# IMX_Supporting_Circuits.net
KiCad netlist of a schematic drawn in Altium Designer
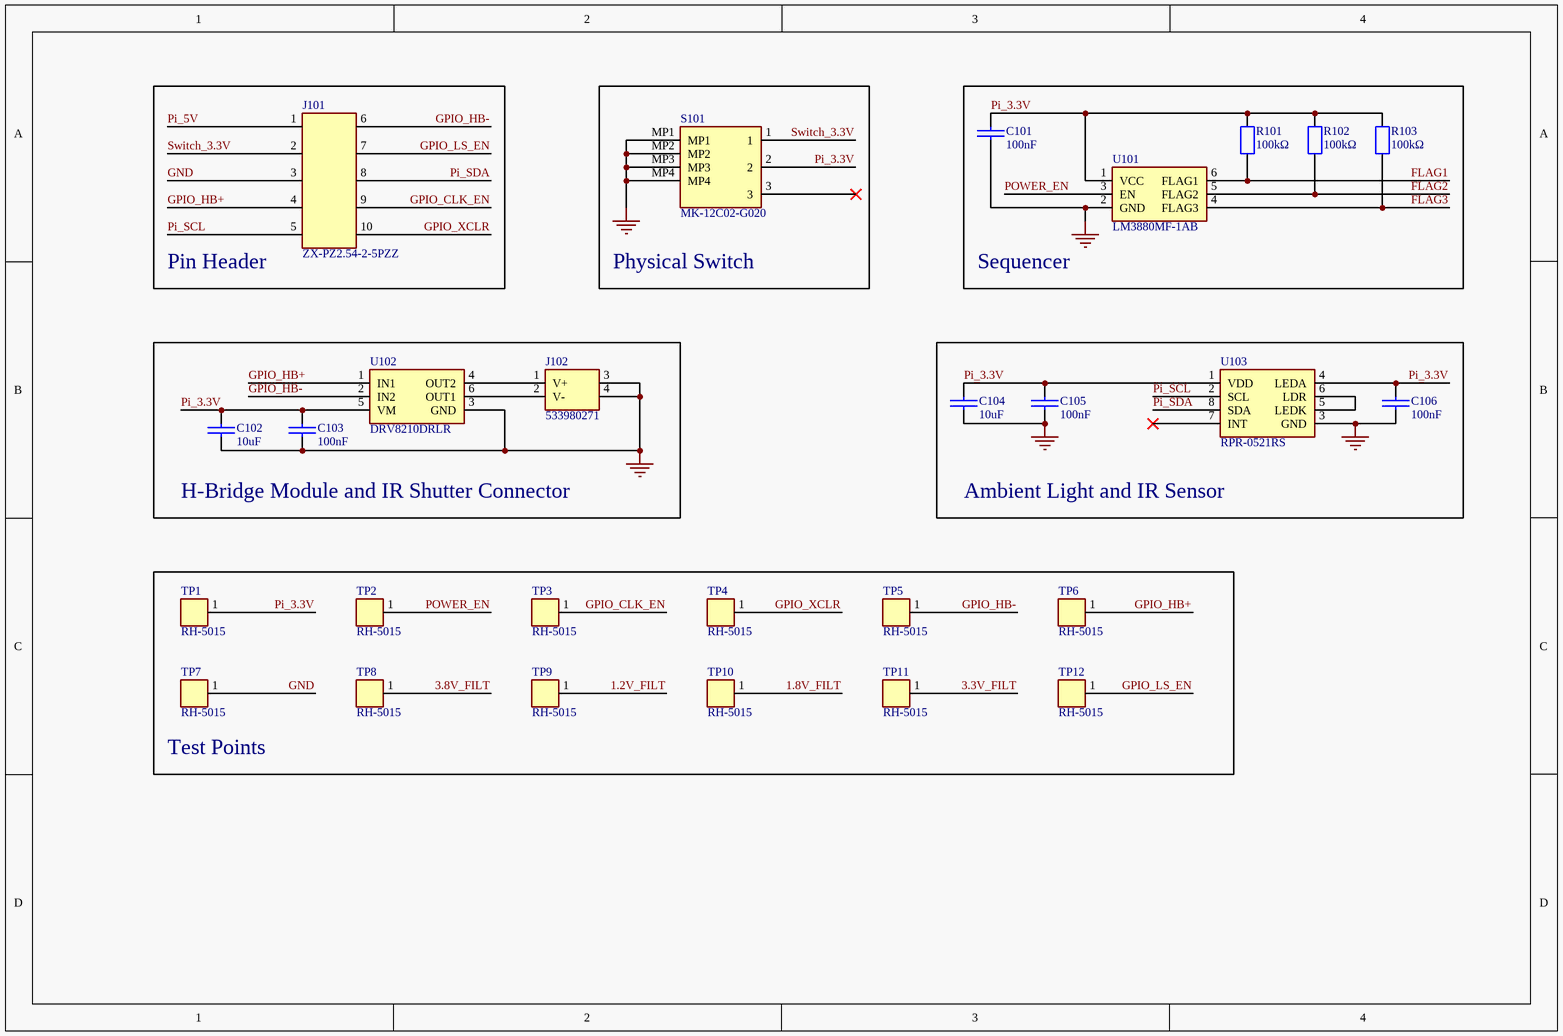
[diagram p0: IMX_Supporting Circuits.SchDoc]

(export (version "E")
  (design (tool "Eeschema 10.0.6"))
  (components
    (comp (ref "C101")
      (value "100nF")
      (footprint "Capacitor, 0402")
      (description "Ceramic Capacitor, 16V, 10% +/- Tol, X7R, 0.1uF, SMD, 0402, #CL05B104KO5NNNC, JLC#C1525")
      (libsource (lib "Component Library") (part "Capacitor, 0402, 100nF"))
    )
    (comp (ref "C102")
      (value "10uF")
      (footprint "Capacitor, 0603")
      (description "Ceramic Capacitor, 10V, 10% +/- Tol, X7R, 10uF, SMD, 0603, #GRM188Z71A106KA73D, JLC#C2959727")
      (libsource (lib "Component Library") (part "Capacitor, 0603, 10uF"))
    )
    (comp (ref "C103")
      (value "100nF")
      (footprint "Capacitor, 0402")
      (description "Ceramic Capacitor, 16V, 10% +/- Tol, X7R, 0.1uF, SMD, 0402, #CL05B104KO5NNNC, JLC#C1525")
      (libsource (lib "Component Library") (part "Capacitor, 0402, 100nF"))
    )
    (comp (ref "C104")
      (value "10uF")
      (footprint "Capacitor, 0603")
      (description "Ceramic Capacitor, 10V, 10% +/- Tol, X7R, 10uF, SMD, 0603, #GRM188Z71A106KA73D, JLC#C2959727")
      (libsource (lib "Component Library") (part "Capacitor, 0603, 10uF"))
    )
    (comp (ref "C105")
      (value "100nF")
      (footprint "Capacitor, 0402")
      (description "Ceramic Capacitor, 16V, 10% +/- Tol, X7R, 0.1uF, SMD, 0402, #CL05B104KO5NNNC, JLC#C1525")
      (libsource (lib "Component Library") (part "Capacitor, 0402, 100nF"))
    )
    (comp (ref "C106")
      (value "100nF")
      (footprint "Capacitor, 0402")
      (description "Ceramic Capacitor, 16V, 10% +/- Tol, X7R, 0.1uF, SMD, 0402, #CL05B104KO5NNNC, JLC#C1525")
      (libsource (lib "Component Library") (part "Capacitor, 0402, 100nF"))
    )
    (comp (ref "J101")
      (value "ZX-PZ2.54-2-5PZZ")
      (footprint "Pin Header, DIP 2x5, 2.54mm")
      (libsource (lib "Component Library") (part "Pin Header, DIP 2x5, 2.54mm"))
    )
    (comp (ref "J102")
      (value "533980271")
      (footprint "Molex PicoBlade, Wire To Board 1x2, 533980271")
      (libsource (lib "Component Library") (part "Molex PicoBlade, Wire To Board 1x2"))
    )
    (comp (ref "R101")
      (value "100kΩ")
      (footprint "Resistor, 0603, Yageo")
      (description "Thick Film Resistor, ±1%, ±100ppm/℃, -55℃~+155℃, 0603, 100kΩ, #RC0603FR-07100KL, JLC#C14675")
      (libsource (lib "Component Library") (part "Resistor, 0603, 100kΩ"))
    )
    (comp (ref "R102")
      (value "100kΩ")
      (footprint "Resistor, 0603, Yageo")
      (description "Thick Film Resistor, ±1%, ±100ppm/℃, -55℃~+155℃, 0603, 100kΩ, #RC0603FR-07100KL, JLC#C14675")
      (libsource (lib "Component Library") (part "Resistor, 0603, 100kΩ"))
    )
    (comp (ref "R103")
      (value "100kΩ")
      (footprint "Resistor, 0603, Yageo")
      (description "Thick Film Resistor, ±1%, ±100ppm/℃, -55℃~+155℃, 0603, 100kΩ, #RC0603FR-07100KL, JLC#C14675")
      (libsource (lib "Component Library") (part "Resistor, 0603, 100kΩ"))
    )
    (comp (ref "S101")
      (value "MK-12C02-G020")
      (footprint "Swich, 1A, Single Pole Double Throw, MK-12C02-G020")
      (libsource (lib "Component Library") (part "Swich, 1A, Single Pole Double Throw"))
    )
    (comp (ref "TP1")
      (value "RH-5015")
      (footprint "Test Point")
      (description "Pogo Pin Spring Probe Connector ROHS, #RH-5015, JLC#C5199798")
      (libsource (lib "Component Library") (part "Test Ring"))
    )
    (comp (ref "TP2")
      (value "RH-5015")
      (footprint "Test Point")
      (description "Pogo Pin Spring Probe Connector ROHS, #RH-5015, JLC#C5199798")
      (libsource (lib "Component Library") (part "Test Ring"))
    )
    (comp (ref "TP3")
      (value "RH-5015")
      (footprint "Test Point")
      (description "Pogo Pin Spring Probe Connector ROHS, #RH-5015, JLC#C5199798")
      (libsource (lib "Component Library") (part "Test Ring"))
    )
    (comp (ref "TP4")
      (value "RH-5015")
      (footprint "Test Point")
      (description "Pogo Pin Spring Probe Connector ROHS, #RH-5015, JLC#C5199798")
      (libsource (lib "Component Library") (part "Test Ring"))
    )
    (comp (ref "TP5")
      (value "RH-5015")
      (footprint "Test Point")
      (description "Pogo Pin Spring Probe Connector ROHS, #RH-5015, JLC#C5199798")
      (libsource (lib "Component Library") (part "Test Ring"))
    )
    (comp (ref "TP6")
      (value "RH-5015")
      (footprint "Test Point")
      (description "Pogo Pin Spring Probe Connector ROHS, #RH-5015, JLC#C5199798")
      (libsource (lib "Component Library") (part "Test Ring"))
    )
    (comp (ref "TP7")
      (value "RH-5015")
      (footprint "Test Point")
      (description "Pogo Pin Spring Probe Connector ROHS, #RH-5015, JLC#C5199798")
      (libsource (lib "Component Library") (part "Test Ring"))
    )
    (comp (ref "TP8")
      (value "RH-5015")
      (footprint "Test Point")
      (description "Pogo Pin Spring Probe Connector ROHS, #RH-5015, JLC#C5199798")
      (libsource (lib "Component Library") (part "Test Ring"))
    )
    (comp (ref "TP9")
      (value "RH-5015")
      (footprint "Test Point")
      (description "Pogo Pin Spring Probe Connector ROHS, #RH-5015, JLC#C5199798")
      (libsource (lib "Component Library") (part "Test Ring"))
    )
    (comp (ref "TP10")
      (value "RH-5015")
      (footprint "Test Point")
      (description "Pogo Pin Spring Probe Connector ROHS, #RH-5015, JLC#C5199798")
      (libsource (lib "Component Library") (part "Test Ring"))
    )
    (comp (ref "TP11")
      (value "RH-5015")
      (footprint "Test Point")
      (description "Pogo Pin Spring Probe Connector ROHS, #RH-5015, JLC#C5199798")
      (libsource (lib "Component Library") (part "Test Ring"))
    )
    (comp (ref "TP12")
      (value "RH-5015")
      (footprint "Test Point")
      (description "Pogo Pin Spring Probe Connector ROHS, #RH-5015, JLC#C5199798")
      (libsource (lib "Component Library") (part "Test Ring"))
    )
    (comp (ref "U101")
      (value "LM3880MF-1AB")
      (footprint "Sequencer, SOT-23")
      (description "USON-6-EP(2.1x2.1) Ambient Light Sensors ROHS, JLC#C701867")
      (fields
        (field (name "MANUFACTURER_PART_NUMBER") "LM3880MF-1AB/NOPB")
        (field (name "MOUSER PART NUMBER") "926-LM3880MF1ABNOPB")
      )
      (libsource (lib "Component Library") (part "Sequencer, 3 Flags, 30ms, 1-2-3/3-2-1"))
    )
    (comp (ref "U102")
      (value "DRV8210DRLR")
      (footprint "H-Bridge, SOT-563")
      (description "SOT-563 Relay / Coil Drivers ROHS, #DRV8210DRLR, JLC#C3681297")
      (libsource (lib "Component Library") (part "H-Bridge, SOT-563"))
    )
    (comp (ref "U103")
      (value "RPR-0521RS")
      (footprint "Rohm ALS")
      (description "SMD-8P Ambient Light Sensors ROHS, JLC#C509781")
      (libsource (lib "Component Library") (part "Rohm ALS"))
    )
  )
  (nets
    (net (code "1") (name "/1.2V_FILT") (class "Default")
      (node (ref "TP9") (pin "1") (pinfunction "1_1") (pintype "passive"))
    )
    (net (code "2") (name "/1.8V_FILT") (class "Default")
      (node (ref "TP10") (pin "1") (pinfunction "1_1") (pintype "passive"))
    )
    (net (code "3") (name "/3.3V_FILT") (class "Default")
      (node (ref "TP11") (pin "1") (pinfunction "1_1") (pintype "passive"))
    )
    (net (code "4") (name "/3.8V_FILT") (class "Default")
      (node (ref "TP8") (pin "1") (pinfunction "1_1") (pintype "passive"))
    )
    (net (code "5") (name "/FLAG1") (class "Default")
      (node (ref "R101") (pin "1") (pintype "passive"))
      (node (ref "U101") (pin "6") (pinfunction "FLAG1_6") (pintype "passive"))
    )
    (net (code "6") (name "/FLAG2") (class "Default")
      (node (ref "R102") (pin "1") (pintype "passive"))
      (node (ref "U101") (pin "5") (pinfunction "FLAG2_5") (pintype "passive"))
    )
    (net (code "7") (name "/FLAG3") (class "Default")
      (node (ref "R103") (pin "1") (pintype "passive"))
      (node (ref "U101") (pin "4") (pinfunction "FLAG3_4") (pintype "passive"))
    )
    (net (code "8") (name "/GPIO_CLK_EN") (class "Default")
      (node (ref "J101") (pin "9") (pintype "bidirectional"))
      (node (ref "TP3") (pin "1") (pinfunction "1_1") (pintype "passive"))
    )
    (net (code "9") (name "/GPIO_HB+") (class "Default")
      (node (ref "J101") (pin "4") (pintype "passive"))
      (node (ref "TP6") (pin "1") (pinfunction "1_1") (pintype "passive"))
      (node (ref "U102") (pin "1") (pinfunction "IN1_1") (pintype "passive"))
    )
    (net (code "10") (name "/GPIO_HB-") (class "Default")
      (node (ref "J101") (pin "6") (pintype "passive"))
      (node (ref "TP5") (pin "1") (pinfunction "1_1") (pintype "passive"))
      (node (ref "U102") (pin "2") (pinfunction "IN2_2") (pintype "passive"))
    )
    (net (code "11") (name "/GPIO_LS_EN") (class "Default")
      (node (ref "J101") (pin "7") (pintype "passive"))
      (node (ref "TP12") (pin "1") (pinfunction "1_1") (pintype "passive"))
    )
    (net (code "12") (name "/GPIO_XCLR") (class "Default")
      (node (ref "J101") (pin "10") (pintype "bidirectional"))
      (node (ref "TP4") (pin "1") (pinfunction "1_1") (pintype "passive"))
    )
    (net (code "13") (name "/POWER_EN") (class "Default")
      (node (ref "TP2") (pin "1") (pinfunction "1_1") (pintype "passive"))
      (node (ref "U101") (pin "3") (pinfunction "EN_3") (pintype "passive"))
    )
    (net (code "14") (name "/Pi_3.3V") (class "Default")
      (node (ref "C101") (pin "1") (pinfunction "1_1") (pintype "passive"))
      (node (ref "C102") (pin "1") (pinfunction "1_1") (pintype "passive"))
      (node (ref "C103") (pin "1") (pinfunction "1_1") (pintype "passive"))
      (node (ref "C104") (pin "1") (pinfunction "1_1") (pintype "passive"))
      (node (ref "C105") (pin "1") (pinfunction "1_1") (pintype "passive"))
      (node (ref "C106") (pin "1") (pinfunction "1_1") (pintype "passive"))
      (node (ref "R101") (pin "2") (pintype "passive"))
      (node (ref "R102") (pin "2") (pintype "passive"))
      (node (ref "R103") (pin "2") (pintype "passive"))
      (node (ref "S101") (pin "2") (pinfunction "2_2") (pintype "passive"))
      (node (ref "TP1") (pin "1") (pinfunction "1_1") (pintype "passive"))
      (node (ref "U101") (pin "1") (pinfunction "VCC_1") (pintype "passive"))
      (node (ref "U102") (pin "5") (pinfunction "VM_5") (pintype "passive"))
      (node (ref "U103") (pin "1") (pinfunction "VDD_1") (pintype "passive"))
      (node (ref "U103") (pin "4") (pinfunction "LEDA_4") (pintype "passive"))
    )
    (net (code "15") (name "/Pi_5V") (class "Default") (node (ref "J101") (pin "1") (pintype "passive")))
    (net (code "16") (name "/Pi_SCL") (class "Default")
      (node (ref "J101") (pin "5") (pintype "passive"))
      (node (ref "U103") (pin "2") (pinfunction "SCL_2") (pintype "passive"))
    )
    (net (code "17") (name "/Pi_SDA") (class "Default")
      (node (ref "J101") (pin "8") (pintype "bidirectional"))
      (node (ref "U103") (pin "8") (pinfunction "SDA_8") (pintype "passive"))
    )
    (net (code "18") (name "/Switch_3.3V") (class "Default")
      (node (ref "J101") (pin "2") (pintype "passive"))
      (node (ref "S101") (pin "1") (pinfunction "1_1") (pintype "passive"))
    )
    (net (code "19") (name "GND") (class "Default")
      (node (ref "C101") (pin "2") (pinfunction "2_2") (pintype "passive"))
      (node (ref "C102") (pin "2") (pinfunction "2_2") (pintype "passive"))
      (node (ref "C103") (pin "2") (pinfunction "2_2") (pintype "passive"))
      (node (ref "C104") (pin "2") (pinfunction "2_2") (pintype "passive"))
      (node (ref "C105") (pin "2") (pinfunction "2_2") (pintype "passive"))
      (node (ref "C106") (pin "2") (pinfunction "2_2") (pintype "passive"))
      (node (ref "J101") (pin "3") (pintype "passive"))
      (node (ref "J102") (pin "3") (pintype "passive"))
      (node (ref "J102") (pin "4") (pintype "passive"))
      (node (ref "S101") (pin "MP1") (pinfunction "MP1_MP1") (pintype "passive"))
      (node (ref "S101") (pin "MP2") (pinfunction "MP2_MP2") (pintype "passive"))
      (node (ref "S101") (pin "MP3") (pinfunction "MP3_MP3") (pintype "passive"))
      (node (ref "S101") (pin "MP4") (pinfunction "MP4_MP4") (pintype "passive"))
      (node (ref "TP7") (pin "1") (pinfunction "1_1") (pintype "passive"))
      (node (ref "U101") (pin "2") (pinfunction "GND_2") (pintype "passive"))
      (node (ref "U102") (pin "3") (pinfunction "GND_3") (pintype "passive"))
      (node (ref "U103") (pin "3") (pinfunction "GND_3") (pintype "passive"))
    )
    (net (code "20") (name "Net-(J102-V+)") (class "Default")
      (node (ref "J102") (pin "1") (pinfunction "V+_1") (pintype "passive"))
      (node (ref "U102") (pin "4") (pinfunction "OUT2_4") (pintype "passive"))
    )
    (net (code "21") (name "Net-(J102-V-)") (class "Default")
      (node (ref "J102") (pin "2") (pinfunction "V-_2") (pintype "passive"))
      (node (ref "U102") (pin "6") (pinfunction "OUT1_6") (pintype "passive"))
    )
    (net (code "22") (name "Net-(U103-LDR)") (class "Default")
      (node (ref "U103") (pin "5") (pinfunction "LEDK_5") (pintype "passive"))
      (node (ref "U103") (pin "6") (pinfunction "LDR_6") (pintype "passive"))
    )
    (net (code "23") (name "unconnected-(S101-Pad3)") (class "Default")
      (node (ref "S101") (pin "3") (pinfunction "3_3") (pintype "passive+no_connect"))
    )
    (net (code "24") (name "unconnected-(U103-INT-Pad7)") (class "Default")
      (node (ref "U103") (pin "7") (pinfunction "INT_7") (pintype "passive+no_connect"))
    )
  )
)
